# PWR_SRC.net
KiCad netlist of a schematic drawn in Altium Designer
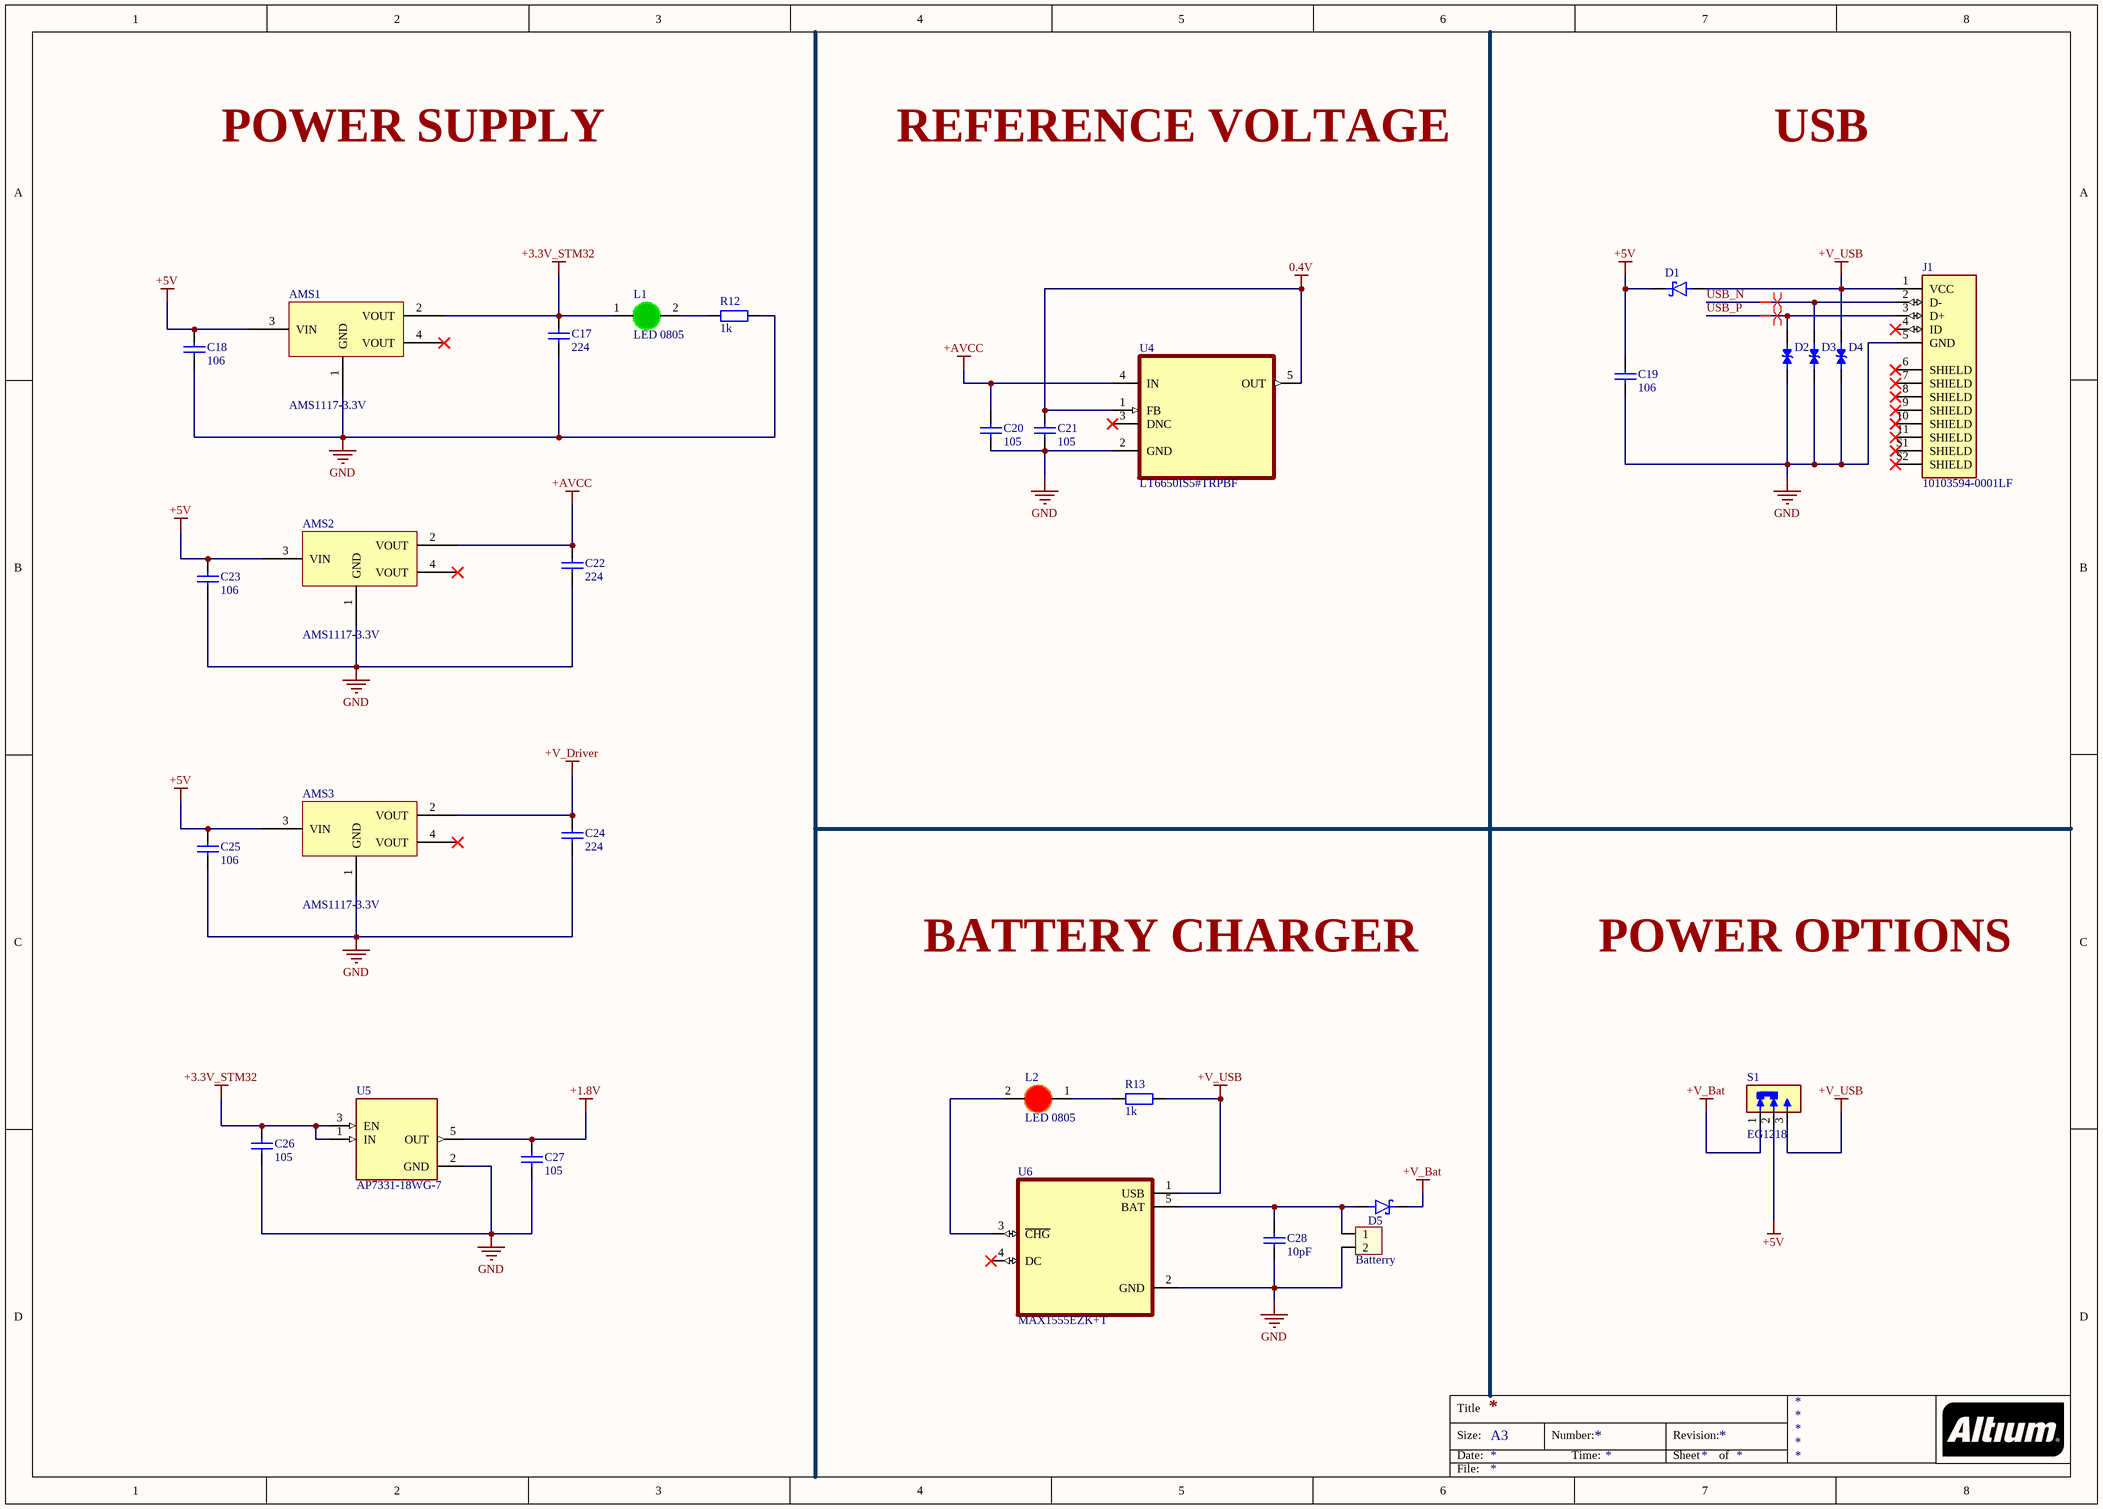
[diagram p0: PWR_SRC.SchDoc]

(export (version "E")
  (design (tool "Eeschema 10.0.6"))
  (components
    (comp (ref "AMS1")
      (value "AMS1117-3.3V")
      (footprint "SOT223")
      (description "Dán")
      (libsource (lib "Altium_Lib_by_KhueNguyenCreator") (part "AMS1117 SMD"))
    )
    (comp (ref "AMS2")
      (value "AMS1117-3.3V")
      (footprint "SOT223")
      (description "Dán")
      (libsource (lib "Altium_Lib_by_KhueNguyenCreator") (part "AMS1117 SMD"))
    )
    (comp (ref "AMS3")
      (value "AMS1117-3.3V")
      (footprint "SOT223")
      (description "Dán")
      (libsource (lib "Altium_Lib_by_KhueNguyenCreator") (part "AMS1117 SMD"))
    )
    (comp (ref "Batterry1")
      (value "Batterry")
      (footprint "XH2.54M-2")
      (description "Cắm")
      (libsource (lib "Altium_Lib_by_KhueNguyenCreator") (part "Header 2P 2.54 Duc Thang"))
    )
    (comp (ref "C17")
      (value "224")
      (footprint "tu 0805")
      (description "Dán")
      (libsource (lib "Altium_Lib_by_KhueNguyenCreator") (part "Tu 0805 224 50V 10%"))
    )
    (comp (ref "C18")
      (value "106")
      (footprint "tu 0603")
      (description "Dán")
      (libsource (lib "Altium_Lib_by_KhueNguyenCreator") (part "Tu 0603 106 16V 20%"))
    )
    (comp (ref "C19")
      (value "106")
      (footprint "tu 0603")
      (description "Dán")
      (libsource (lib "Altium_Lib_by_KhueNguyenCreator") (part "Tu 0603 106 16V 20%"))
    )
    (comp (ref "C20")
      (value "105")
      (footprint "tu 0603")
      (description "Dán")
      (libsource (lib "Altium_Lib_by_KhueNguyenCreator") (part "Tu 0603 105 16V 20%"))
    )
    (comp (ref "C21")
      (value "105")
      (footprint "tu 0603")
      (description "Dán")
      (libsource (lib "Altium_Lib_by_KhueNguyenCreator") (part "Tu 0603 105 16V 20%"))
    )
    (comp (ref "C22")
      (value "224")
      (footprint "tu 0805")
      (description "Dán")
      (libsource (lib "Altium_Lib_by_KhueNguyenCreator") (part "Tu 0805 224 50V 10%"))
    )
    (comp (ref "C23")
      (value "106")
      (footprint "tu 0603")
      (description "Dán")
      (libsource (lib "Altium_Lib_by_KhueNguyenCreator") (part "Tu 0603 106 16V 20%"))
    )
    (comp (ref "C24")
      (value "224")
      (footprint "tu 0805")
      (description "Dán")
      (libsource (lib "Altium_Lib_by_KhueNguyenCreator") (part "Tu 0805 224 50V 10%"))
    )
    (comp (ref "C25")
      (value "106")
      (footprint "tu 0603")
      (description "Dán")
      (libsource (lib "Altium_Lib_by_KhueNguyenCreator") (part "Tu 0603 106 16V 20%"))
    )
    (comp (ref "C26")
      (value "105")
      (footprint "tu 0603")
      (description "Dán")
      (libsource (lib "Altium_Lib_by_KhueNguyenCreator") (part "Tu 0603 105 16V 20%"))
    )
    (comp (ref "C27")
      (value "105")
      (footprint "tu 0603")
      (description "Dán")
      (libsource (lib "Altium_Lib_by_KhueNguyenCreator") (part "Tu 0603 105 16V 20%"))
    )
    (comp (ref "C28")
      (value "10pF")
      (footprint "tu 0805")
      (description "Dán")
      (libsource (lib "Altium_Lib_by_KhueNguyenCreator") (part "Tu 0805 10pF 50V 10%"))
    )
    (comp (ref "D1")
      (value "1N5819HW-7-F")
      (footprint "SOD3715X145N")
      (description "1N5819HW Series 40 V 1 A Surface Mount Schottky Barrier Rectifier - SOD-123")
      (fields (field (name "MF") "{'manufacturer': u'Diodes Inc.'}"))
      (libsource (lib "SnapEDA_Library") (part "1N5819HW-7-F"))
    )
    (comp (ref "D2")
      (value "LESD5D5.0CT1G")
      (footprint "TVS_LESD5D5.0CT1G")
      (fields (field (name "MF") "{'manufacturer': u'Leshan Radio Co.'}"))
      (libsource (lib "SnapEDA_Library") (part "LESD5D5.0CT1G"))
    )
    (comp (ref "D3")
      (value "LESD5D5.0CT1G")
      (footprint "TVS_LESD5D5.0CT1G")
      (fields (field (name "MF") "{'manufacturer': u'Leshan Radio Co.'}"))
      (libsource (lib "SnapEDA_Library") (part "LESD5D5.0CT1G"))
    )
    (comp (ref "D4")
      (value "LESD5D5.0CT1G")
      (footprint "TVS_LESD5D5.0CT1G")
      (fields (field (name "MF") "{'manufacturer': u'Leshan Radio Co.'}"))
      (libsource (lib "SnapEDA_Library") (part "LESD5D5.0CT1G"))
    )
    (comp (ref "D5")
      (value "1N5819HW-7-F")
      (footprint "SOD3715X145N")
      (description "1N5819HW Series 40 V 1 A Surface Mount Schottky Barrier Rectifier - SOD-123")
      (fields (field (name "MF") "{'manufacturer': u'Diodes Inc.'}"))
      (libsource (lib "SnapEDA_Library") (part "1N5819HW-7-F"))
    )
    (comp (ref "J1")
      (value "10103594-0001LF")
      (footprint "AMPHENOL_10103594-0001LF")
      (description "USB - micro B USB 2.0 Receptacle Connector 5 Position Surface Mount, Right Angle; Through Hole")
      (fields (field (name "MF") "{'manufacturer': u'FCI Connectors'}"))
      (libsource (lib "SnapEDA_Library") (part "10103594-0001LF"))
    )
    (comp (ref "L1")
      (value "LED 0805")
      (footprint "LED-0805-Green")
      (description "Dán")
      (libsource (lib "Altium_Lib_by_KhueNguyenCreator") (part "LED 0805 Xanh La"))
    )
    (comp (ref "L2")
      (value "LED 0805")
      (footprint "LED-0805-Red")
      (description "Dán")
      (libsource (lib "Altium_Lib_by_KhueNguyenCreator") (part "LED 0805 Do"))
    )
    (comp (ref "R12")
      (value "1k")
      (footprint "tro smd 0603")
      (description "Dán")
      (libsource (lib "Altium_Lib_by_KhueNguyenCreator") (part "Tro 0603 5% 1k"))
    )
    (comp (ref "R13")
      (value "1k")
      (footprint "tro smd 0603")
      (description "Dán")
      (libsource (lib "Altium_Lib_by_KhueNguyenCreator") (part "Tro 0603 1% 1k"))
    )
    (comp (ref "S1")
      (value "EG1218")
      (footprint "SW_EG1218")
      (description "Slide Switch, EG Series, SPDT, Non-Shorting, ON-ON, 200mA DC, 30VDC, PC Pin ¦ E-Switch EG1218")
      (fields (field (name "MF") "E-Switch"))
      (libsource (lib "EG1218") (part "EG1218"))
    )
    (comp (ref "U4")
      (value "LT6650IS5#TRPBF")
      (footprint "SOT95P280X100-5N")
      (description "Micropower, 400mV Reference with Rail-to-Rail Buffer Amplifier")
      (fields (field (name "MF") "{'manufacturer': u'Analog Devices'}"))
      (libsource (lib "SnapEDA_Library") (part "LT6650IS5#TRPBF"))
    )
    (comp (ref "U5")
      (value "AP7331-18WG-7")
      (footprint "SOT95P285X145-5N")
      (description "LDO Regulator Pos 1.8V 0.3A 5-Pin SOT-25 T/R")
      (fields (field (name "MF") "{'manufacturer': u'Diodes Inc.'}"))
      (libsource (lib "SnapEDA_Library") (part "AP7331-18WG-7"))
    )
    (comp (ref "U6")
      (value "MAX1555EZK+T")
      (footprint "SOT95P275X110-5N")
      (fields (field (name "MF") "{'manufacturer': u'Analog Devices'}") (field (name "MP") "MAX1555EZK+"))
      (libsource (lib "SnapEDA_Library") (part "MAX1555EZK+T"))
    )
  )
  (nets
    (net (code "1") (name "+1.8V") (class "Default")
      (node (ref "C27") (pin "1") (pinfunction "1_1") (pintype "passive"))
      (node (ref "U5") (pin "5") (pinfunction "OUT_5") (pintype "output"))
    )
    (net (code "2") (name "+3.3V_STM32") (class "Default")
      (node (ref "AMS1") (pin "2") (pinfunction "VOUT_2") (pintype "passive"))
      (node (ref "C17") (pin "1") (pinfunction "1_1") (pintype "passive"))
      (node (ref "C26") (pin "1") (pinfunction "1_1") (pintype "passive"))
      (node (ref "L1") (pin "1") (pinfunction "A_1") (pintype "passive"))
      (node (ref "U5") (pin "1") (pinfunction "IN_1") (pintype "input"))
      (node (ref "U5") (pin "3") (pinfunction "EN_3") (pintype "input"))
    )
    (net (code "3") (name "+5V") (class "Default")
      (node (ref "AMS1") (pin "3") (pinfunction "VIN_3") (pintype "passive"))
      (node (ref "AMS2") (pin "3") (pinfunction "VIN_3") (pintype "passive"))
      (node (ref "AMS3") (pin "3") (pinfunction "VIN_3") (pintype "passive"))
      (node (ref "C18") (pin "1") (pinfunction "1_1") (pintype "passive"))
      (node (ref "C19") (pin "1") (pinfunction "1_1") (pintype "passive"))
      (node (ref "C23") (pin "1") (pinfunction "1_1") (pintype "passive"))
      (node (ref "C25") (pin "1") (pinfunction "1_1") (pintype "passive"))
      (node (ref "D1") (pin "C") (pinfunction "K_C") (pintype "passive"))
      (node (ref "S1") (pin "2") (pinfunction "COM_2") (pintype "passive"))
    )
    (net (code "4") (name "+AVCC") (class "Default")
      (node (ref "AMS2") (pin "2") (pinfunction "VOUT_2") (pintype "passive"))
      (node (ref "C20") (pin "1") (pinfunction "1_1") (pintype "passive"))
      (node (ref "C22") (pin "1") (pinfunction "1_1") (pintype "passive"))
      (node (ref "U4") (pin "4") (pinfunction "IN_4") (pintype "power_in"))
    )
    (net (code "5") (name "+V_Bat") (class "Default")
      (node (ref "D5") (pin "C") (pinfunction "K_C") (pintype "passive"))
      (node (ref "S1") (pin "1") (pinfunction "NC_1") (pintype "passive"))
    )
    (net (code "6") (name "+V_Driver") (class "Default")
      (node (ref "AMS3") (pin "2") (pinfunction "VOUT_2") (pintype "passive"))
      (node (ref "C24") (pin "1") (pinfunction "1_1") (pintype "passive"))
    )
    (net (code "7") (name "+V_USB") (class "Default")
      (node (ref "D1") (pin "A") (pinfunction "A_A") (pintype "passive"))
      (node (ref "D4") (pin "2") (pinfunction "2_2") (pintype "passive"))
      (node (ref "J1") (pin "1") (pinfunction "VCC_1") (pintype "power_in"))
      (node (ref "R13") (pin "2") (pinfunction "2_2") (pintype "passive"))
      (node (ref "S1") (pin "3") (pinfunction "NO_3") (pintype "passive"))
      (node (ref "U6") (pin "1") (pinfunction "USB_1") (pintype "power_in"))
    )
    (net (code "8") (name "/USB_N") (class "Default")
      (node (ref "D3") (pin "2") (pinfunction "2_2") (pintype "passive"))
      (node (ref "J1") (pin "2") (pinfunction "D-_2") (pintype "bidirectional"))
    )
    (net (code "9") (name "/USB_P") (class "Default")
      (node (ref "D2") (pin "2") (pinfunction "2_2") (pintype "passive"))
      (node (ref "J1") (pin "3") (pinfunction "D+_3") (pintype "bidirectional"))
    )
    (net (code "10") (name "0.4V") (class "Default")
      (node (ref "C21") (pin "1") (pinfunction "1_1") (pintype "passive"))
      (node (ref "U4") (pin "1") (pinfunction "FB_1") (pintype "input"))
      (node (ref "U4") (pin "5") (pinfunction "OUT_5") (pintype "output"))
    )
    (net (code "11") (name "GND") (class "Default")
      (node (ref "AMS1") (pin "1") (pinfunction "GND_1") (pintype "passive"))
      (node (ref "AMS2") (pin "1") (pinfunction "GND_1") (pintype "passive"))
      (node (ref "AMS3") (pin "1") (pinfunction "GND_1") (pintype "passive"))
      (node (ref "Batterry1") (pin "2") (pinfunction "2_2") (pintype "passive"))
      (node (ref "C17") (pin "2") (pinfunction "2_2") (pintype "passive"))
      (node (ref "C18") (pin "2") (pinfunction "2_2") (pintype "passive"))
      (node (ref "C19") (pin "2") (pinfunction "2_2") (pintype "passive"))
      (node (ref "C20") (pin "2") (pinfunction "2_2") (pintype "passive"))
      (node (ref "C21") (pin "2") (pinfunction "2_2") (pintype "passive"))
      (node (ref "C22") (pin "2") (pinfunction "2_2") (pintype "passive"))
      (node (ref "C23") (pin "2") (pinfunction "2_2") (pintype "passive"))
      (node (ref "C24") (pin "2") (pinfunction "2_2") (pintype "passive"))
      (node (ref "C25") (pin "2") (pinfunction "2_2") (pintype "passive"))
      (node (ref "C26") (pin "2") (pinfunction "2_2") (pintype "passive"))
      (node (ref "C27") (pin "2") (pinfunction "2_2") (pintype "passive"))
      (node (ref "C28") (pin "2") (pinfunction "2_2") (pintype "passive"))
      (node (ref "D2") (pin "1") (pinfunction "1_1") (pintype "passive"))
      (node (ref "D3") (pin "1") (pinfunction "1_1") (pintype "passive"))
      (node (ref "D4") (pin "1") (pinfunction "1_1") (pintype "passive"))
      (node (ref "J1") (pin "5") (pinfunction "GND_5") (pintype "power_in"))
      (node (ref "R12") (pin "2") (pinfunction "2_2") (pintype "passive"))
      (node (ref "U4") (pin "2") (pinfunction "GND_2") (pintype "passive"))
      (node (ref "U5") (pin "2") (pinfunction "GND_2") (pintype "power_in"))
      (node (ref "U6") (pin "2") (pinfunction "GND_2") (pintype "power_in"))
    )
    (net (code "12") (name "Net-(L1-K)") (class "Default")
      (node (ref "L1") (pin "2") (pinfunction "K_2") (pintype "passive"))
      (node (ref "R12") (pin "1") (pinfunction "1_1") (pintype "passive"))
    )
    (net (code "13") (name "Net-(L2-A)") (class "Default")
      (node (ref "L2") (pin "1") (pinfunction "A_1") (pintype "passive"))
      (node (ref "R13") (pin "1") (pinfunction "1_1") (pintype "passive"))
    )
    (net (code "14") (name "Net-(L2-K)") (class "Default")
      (node (ref "L2") (pin "2") (pinfunction "K_2") (pintype "passive"))
      (node (ref "U6") (pin "3") (pinfunction "~{CHG}_3") (pintype "bidirectional"))
    )
    (net (code "15") (name "Net-(U6-BAT)") (class "Default")
      (node (ref "Batterry1") (pin "1") (pinfunction "1_1") (pintype "passive"))
      (node (ref "C28") (pin "1") (pinfunction "1_1") (pintype "passive"))
      (node (ref "D5") (pin "A") (pinfunction "A_A") (pintype "passive"))
      (node (ref "U6") (pin "5") (pinfunction "BAT_5") (pintype "power_in"))
    )
    (net (code "16") (name "unconnected-(AMS1-VOUT-Pad4)") (class "Default")
      (node (ref "AMS1") (pin "4") (pinfunction "VOUT_4") (pintype "passive+no_connect"))
    )
    (net (code "17") (name "unconnected-(AMS2-VOUT-Pad4)") (class "Default")
      (node (ref "AMS2") (pin "4") (pinfunction "VOUT_4") (pintype "passive+no_connect"))
    )
    (net (code "18") (name "unconnected-(AMS3-VOUT-Pad4)") (class "Default")
      (node (ref "AMS3") (pin "4") (pinfunction "VOUT_4") (pintype "passive+no_connect"))
    )
    (net (code "19") (name "unconnected-(J1-ID-Pad4)") (class "Default")
      (node (ref "J1") (pin "4") (pinfunction "ID_4") (pintype "bidirectional+no_connect"))
    )
    (net (code "20") (name "unconnected-(J1-SHIELD-Pad6)") (class "Default")
      (node (ref "J1") (pin "6") (pinfunction "SHIELD_6") (pintype "passive+no_connect"))
    )
    (net (code "21") (name "unconnected-(J1-SHIELD-Pad7)") (class "Default")
      (node (ref "J1") (pin "7") (pinfunction "SHIELD_7") (pintype "passive+no_connect"))
    )
    (net (code "22") (name "unconnected-(J1-SHIELD-Pad8)") (class "Default")
      (node (ref "J1") (pin "8") (pinfunction "SHIELD_8") (pintype "passive+no_connect"))
    )
    (net (code "23") (name "unconnected-(J1-SHIELD-Pad9)") (class "Default")
      (node (ref "J1") (pin "9") (pinfunction "SHIELD_9") (pintype "passive+no_connect"))
    )
    (net (code "24") (name "unconnected-(J1-SHIELD-Pad10)") (class "Default")
      (node (ref "J1") (pin "10") (pinfunction "SHIELD_10") (pintype "passive+no_connect"))
    )
    (net (code "25") (name "unconnected-(J1-SHIELD-Pad11)") (class "Default")
      (node (ref "J1") (pin "11") (pinfunction "SHIELD_11") (pintype "passive+no_connect"))
    )
    (net (code "26") (name "unconnected-(J1-SHIELD-PadS1)") (class "Default")
      (node (ref "J1") (pin "S1") (pinfunction "SHIELD_S1") (pintype "passive+no_connect"))
    )
    (net (code "27") (name "unconnected-(J1-SHIELD-PadS2)") (class "Default")
      (node (ref "J1") (pin "S2") (pinfunction "SHIELD_S2") (pintype "passive+no_connect"))
    )
    (net (code "28") (name "unconnected-(U4-DNC-Pad3)") (class "Default")
      (node (ref "U4") (pin "3") (pinfunction "DNC_3") (pintype "passive+no_connect"))
    )
    (net (code "29") (name "unconnected-(U6-DC-Pad4)") (class "Default")
      (node (ref "U6") (pin "4") (pinfunction "DC_4") (pintype "bidirectional+no_connect"))
    )
  )
)
